# Atxmega_Board.net
KiCad netlist of a schematic drawn in EAGLE
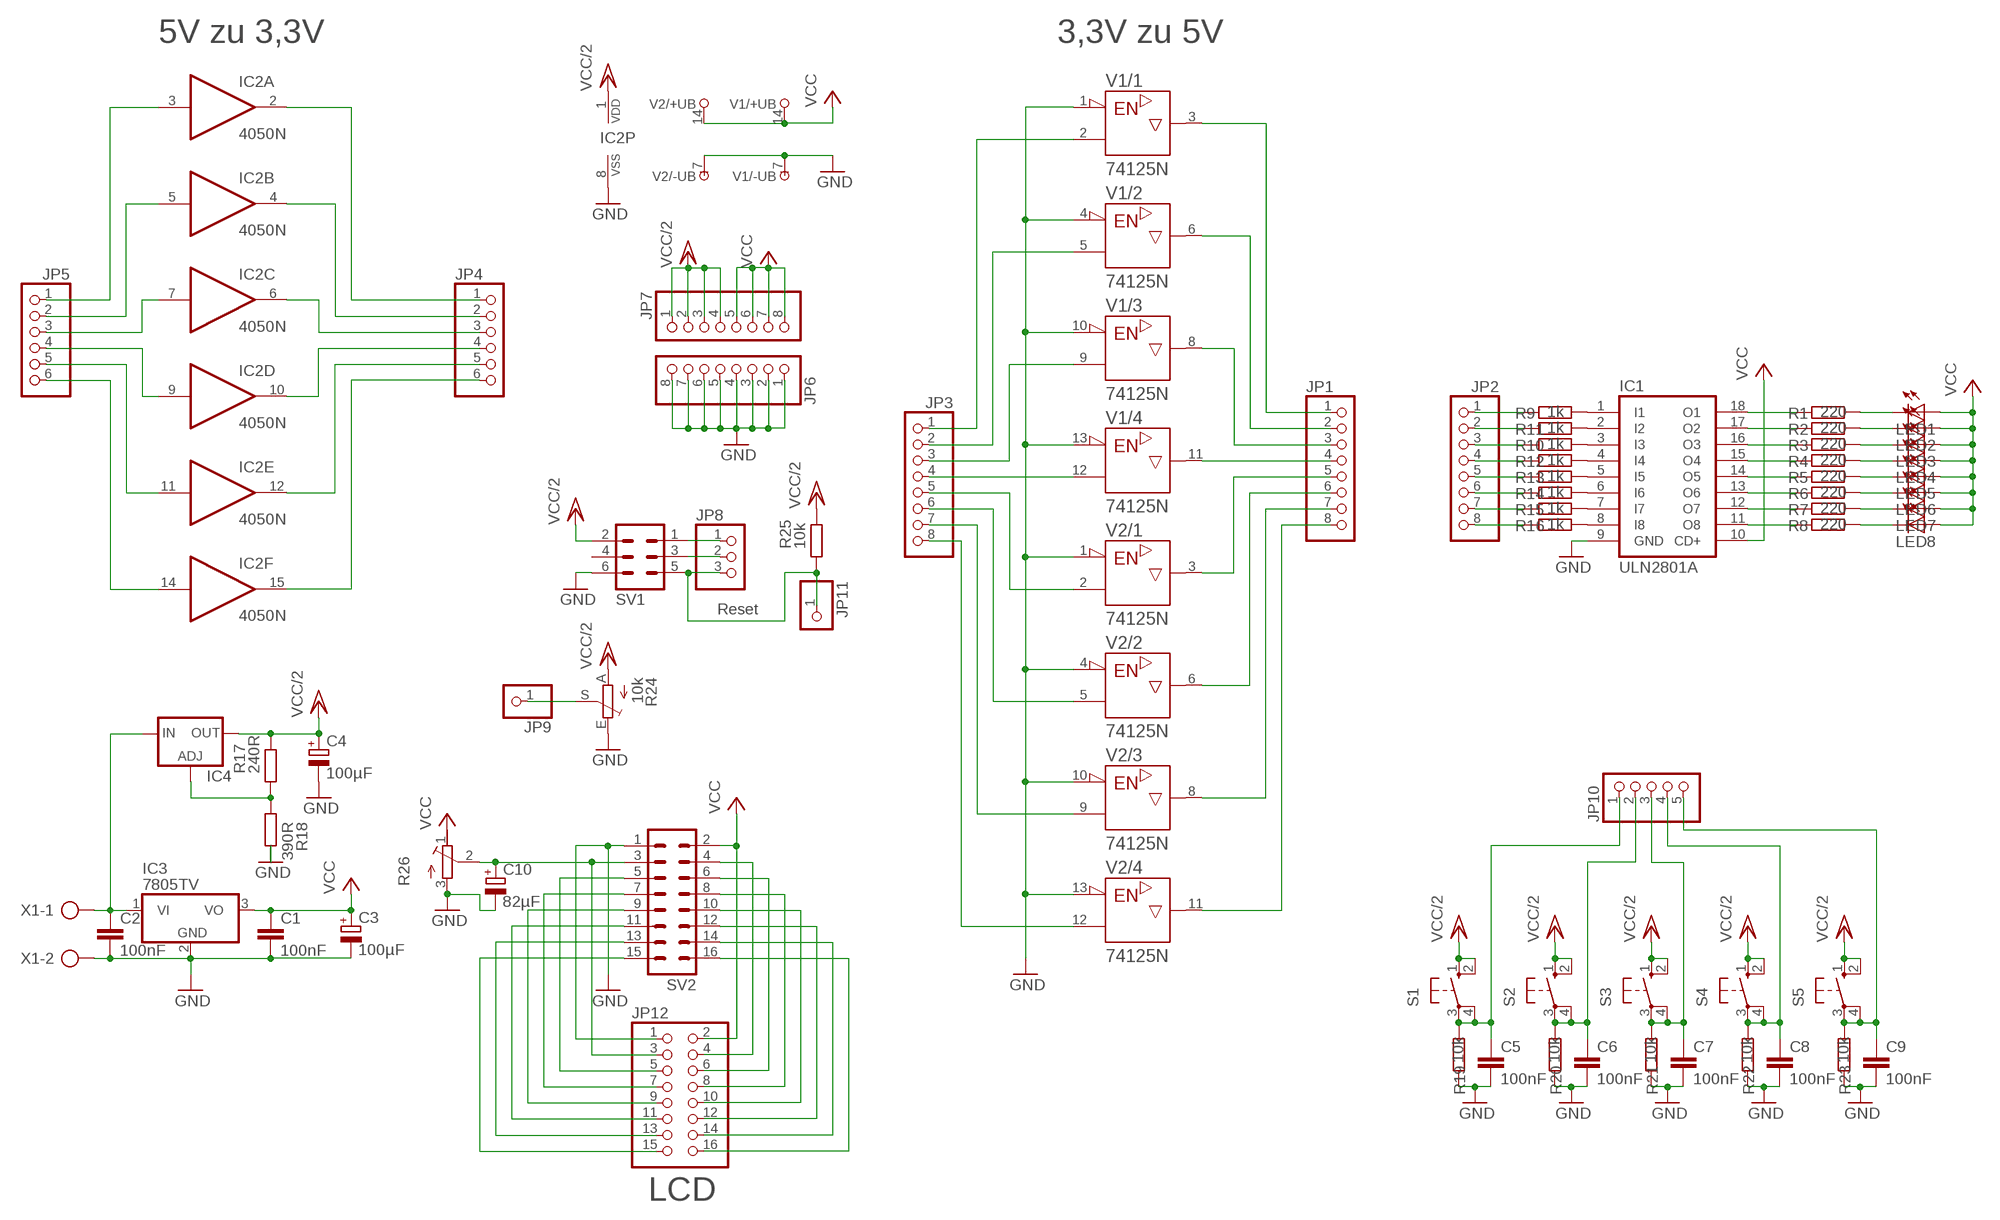
[diagram p0: schematic, sheet 1]

(export (version "E")
  (design (tool "Eeschema 10.0.6"))
  (components
    (comp (ref "C1")
      (value "100nF")
      (footprint "eagle-import:C025_050-025X075")
      (libsource (lib "eagle-import") (part "C-EU025_050-025X075"))
    )
    (comp (ref "C2")
      (value "100nF")
      (footprint "eagle-import:C025_050-025X075")
      (libsource (lib "eagle-import") (part "C-EU025_050-025X075"))
    )
    (comp (ref "C3")
      (value "100µF")
      (footprint "eagle-import:E2,5-7")
      (libsource (lib "eagle-import") (part "CPOL-EUE2.5-7"))
    )
    (comp (ref "C4")
      (value "100µF")
      (footprint "eagle-import:E2,5-7")
      (libsource (lib "eagle-import") (part "CPOL-EUE2.5-7"))
    )
    (comp (ref "C5")
      (value "100nF")
      (footprint "eagle-import:C025_050-025X075")
      (libsource (lib "eagle-import") (part "C-EU025_050-025X075"))
    )
    (comp (ref "C6")
      (value "100nF")
      (footprint "eagle-import:C025_050-025X075")
      (libsource (lib "eagle-import") (part "C-EU025_050-025X075"))
    )
    (comp (ref "C7")
      (value "100nF")
      (footprint "eagle-import:C025_050-025X075")
      (libsource (lib "eagle-import") (part "C-EU025_050-025X075"))
    )
    (comp (ref "C8")
      (value "100nF")
      (footprint "eagle-import:C025_050-025X075")
      (libsource (lib "eagle-import") (part "C-EU025_050-025X075"))
    )
    (comp (ref "C9")
      (value "100nF")
      (footprint "eagle-import:C025_050-025X075")
      (libsource (lib "eagle-import") (part "C-EU025_050-025X075"))
    )
    (comp (ref "C10")
      (value "82µF")
      (footprint "eagle-import:E2,5-7")
      (libsource (lib "eagle-import") (part "CPOL-EUE2.5-7"))
    )
    (comp (ref "IC1")
      (value "ULN2801A")
      (footprint "eagle-import:DIL18")
      (libsource (lib "eagle-import") (part "ULN2801A"))
    )
    (comp (ref "IC2")
      (value "4050N")
      (footprint "eagle-import:DIL16")
      (libsource (lib "eagle-import") (part "4050N"))
    )
    (comp (ref "IC3")
      (value "7805TV")
      (footprint "eagle-import:TO220V")
      (libsource (lib "eagle-import") (part "78TV05"))
    )
    (comp (ref "IC4")
      (value "LM317TS")
      (footprint "eagle-import:317TS")
      (libsource (lib "eagle-import") (part "LM317TS"))
    )
    (comp (ref "JP1")
      (value "PINHD-1X8")
      (footprint "eagle-import:1X08")
      (libsource (lib "eagle-import") (part "PINHD-1X8"))
    )
    (comp (ref "JP2")
      (value "PINHD-1X8")
      (footprint "eagle-import:1X08")
      (libsource (lib "eagle-import") (part "PINHD-1X8"))
    )
    (comp (ref "JP3")
      (value "PINHD-1X8")
      (footprint "eagle-import:1X08")
      (libsource (lib "eagle-import") (part "PINHD-1X8"))
    )
    (comp (ref "JP4")
      (value "PINHD-1X6")
      (footprint "eagle-import:1X06")
      (libsource (lib "eagle-import") (part "PINHD-1X6"))
    )
    (comp (ref "JP5")
      (value "PINHD-1X6")
      (footprint "eagle-import:1X06")
      (libsource (lib "eagle-import") (part "PINHD-1X6"))
    )
    (comp (ref "JP6")
      (value "PINHD-1X8")
      (footprint "eagle-import:1X08")
      (libsource (lib "eagle-import") (part "PINHD-1X8"))
    )
    (comp (ref "JP7")
      (value "PINHD-1X8")
      (footprint "eagle-import:1X08")
      (libsource (lib "eagle-import") (part "PINHD-1X8"))
    )
    (comp (ref "JP8")
      (value "PINHD-1X3")
      (footprint "eagle-import:1X03")
      (libsource (lib "eagle-import") (part "PINHD-1X3"))
    )
    (comp (ref "JP9")
      (value "PINHD-1X1")
      (footprint "eagle-import:1X01")
      (libsource (lib "eagle-import") (part "PINHD-1X1"))
    )
    (comp (ref "JP10")
      (value "PINHD-1X5")
      (footprint "eagle-import:1X05")
      (libsource (lib "eagle-import") (part "PINHD-1X5"))
    )
    (comp (ref "JP11")
      (value "PINHD-1X1")
      (footprint "eagle-import:1X01")
      (libsource (lib "eagle-import") (part "PINHD-1X1"))
    )
    (comp (ref "JP12")
      (value "PINHD-2X8")
      (footprint "eagle-import:2X08")
      (libsource (lib "eagle-import") (part "PINHD-2X8"))
    )
    (comp (ref "LED1")
      (value "LED5MM")
      (footprint "eagle-import:LED5MM")
      (libsource (lib "eagle-import") (part "LED5MM"))
    )
    (comp (ref "LED2")
      (value "LED5MM")
      (footprint "eagle-import:LED5MM")
      (libsource (lib "eagle-import") (part "LED5MM"))
    )
    (comp (ref "LED3")
      (value "LED5MM")
      (footprint "eagle-import:LED5MM")
      (libsource (lib "eagle-import") (part "LED5MM"))
    )
    (comp (ref "LED4")
      (value "LED5MM")
      (footprint "eagle-import:LED5MM")
      (libsource (lib "eagle-import") (part "LED5MM"))
    )
    (comp (ref "LED5")
      (value "LED5MM")
      (footprint "eagle-import:LED5MM")
      (libsource (lib "eagle-import") (part "LED5MM"))
    )
    (comp (ref "LED6")
      (value "LED5MM")
      (footprint "eagle-import:LED5MM")
      (libsource (lib "eagle-import") (part "LED5MM"))
    )
    (comp (ref "LED7")
      (value "LED5MM")
      (footprint "eagle-import:LED5MM")
      (libsource (lib "eagle-import") (part "LED5MM"))
    )
    (comp (ref "LED8")
      (value "LED5MM")
      (footprint "eagle-import:LED5MM")
      (libsource (lib "eagle-import") (part "LED5MM"))
    )
    (comp (ref "R1")
      (value "220")
      (footprint "eagle-import:0207_10")
      (libsource (lib "eagle-import") (part "R-EU_0207/10"))
    )
    (comp (ref "R2")
      (value "220")
      (footprint "eagle-import:0207_10")
      (libsource (lib "eagle-import") (part "R-EU_0207/10"))
    )
    (comp (ref "R3")
      (value "220")
      (footprint "eagle-import:0207_10")
      (libsource (lib "eagle-import") (part "R-EU_0207/10"))
    )
    (comp (ref "R4")
      (value "220")
      (footprint "eagle-import:0207_10")
      (libsource (lib "eagle-import") (part "R-EU_0207/10"))
    )
    (comp (ref "R5")
      (value "220")
      (footprint "eagle-import:0207_10")
      (libsource (lib "eagle-import") (part "R-EU_0207/10"))
    )
    (comp (ref "R6")
      (value "220")
      (footprint "eagle-import:0207_10")
      (libsource (lib "eagle-import") (part "R-EU_0207/10"))
    )
    (comp (ref "R7")
      (value "220")
      (footprint "eagle-import:0207_10")
      (libsource (lib "eagle-import") (part "R-EU_0207/10"))
    )
    (comp (ref "R8")
      (value "220")
      (footprint "eagle-import:0207_10")
      (libsource (lib "eagle-import") (part "R-EU_0207/10"))
    )
    (comp (ref "R9")
      (value "1k")
      (footprint "eagle-import:0207_10")
      (libsource (lib "eagle-import") (part "R-EU_0207/10"))
    )
    (comp (ref "R10")
      (value "1k")
      (footprint "eagle-import:0207_10")
      (libsource (lib "eagle-import") (part "R-EU_0207/10"))
    )
    (comp (ref "R11")
      (value "1k")
      (footprint "eagle-import:0207_10")
      (libsource (lib "eagle-import") (part "R-EU_0207/10"))
    )
    (comp (ref "R12")
      (value "1k")
      (footprint "eagle-import:0207_10")
      (libsource (lib "eagle-import") (part "R-EU_0207/10"))
    )
    (comp (ref "R13")
      (value "1k")
      (footprint "eagle-import:0207_10")
      (libsource (lib "eagle-import") (part "R-EU_0207/10"))
    )
    (comp (ref "R14")
      (value "1k")
      (footprint "eagle-import:0207_10")
      (libsource (lib "eagle-import") (part "R-EU_0207/10"))
    )
    (comp (ref "R15")
      (value "1k")
      (footprint "eagle-import:0207_10")
      (libsource (lib "eagle-import") (part "R-EU_0207/10"))
    )
    (comp (ref "R16")
      (value "1k")
      (footprint "eagle-import:0207_10")
      (libsource (lib "eagle-import") (part "R-EU_0207/10"))
    )
    (comp (ref "R17")
      (value "240R")
      (footprint "eagle-import:0207_10")
      (libsource (lib "eagle-import") (part "R-EU_0207/10"))
    )
    (comp (ref "R18")
      (value "390R")
      (footprint "eagle-import:0207_10")
      (libsource (lib "eagle-import") (part "R-EU_0207/10"))
    )
    (comp (ref "R19")
      (value "10k")
      (footprint "eagle-import:0207_10")
      (libsource (lib "eagle-import") (part "R-EU_0207/10"))
    )
    (comp (ref "R20")
      (value "10k")
      (footprint "eagle-import:0207_10")
      (libsource (lib "eagle-import") (part "R-EU_0207/10"))
    )
    (comp (ref "R21")
      (value "10k")
      (footprint "eagle-import:0207_10")
      (libsource (lib "eagle-import") (part "R-EU_0207/10"))
    )
    (comp (ref "R22")
      (value "10k")
      (footprint "eagle-import:0207_10")
      (libsource (lib "eagle-import") (part "R-EU_0207/10"))
    )
    (comp (ref "R23")
      (value "10k")
      (footprint "eagle-import:0207_10")
      (libsource (lib "eagle-import") (part "R-EU_0207/10"))
    )
    (comp (ref "R24")
      (value "10k")
      (footprint "eagle-import:ST15")
      (libsource (lib "eagle-import") (part "TRIM_EU-ST15"))
    )
    (comp (ref "R25")
      (value "10k")
      (footprint "eagle-import:0207_10")
      (libsource (lib "eagle-import") (part "R-EU_0207/10"))
    )
    (comp (ref "R26")
      (value "R-TRIMM3006P")
      (footprint "eagle-import:RTRIM3006P")
      (libsource (lib "eagle-import") (part "R-TRIMM3006P"))
    )
    (comp (ref "S1")
      (value "10-XX")
      (footprint "eagle-import:B3F-10XX")
      (fields (field (name "MPN") "B3F-1000"))
      (libsource (lib "eagle-import") (part "10-XX"))
    )
    (comp (ref "S2")
      (value "10-XX")
      (footprint "eagle-import:B3F-10XX")
      (fields (field (name "MPN") "B3F-1000"))
      (libsource (lib "eagle-import") (part "10-XX"))
    )
    (comp (ref "S3")
      (value "10-XX")
      (footprint "eagle-import:B3F-10XX")
      (fields (field (name "MPN") "B3F-1000"))
      (libsource (lib "eagle-import") (part "10-XX"))
    )
    (comp (ref "S4")
      (value "10-XX")
      (footprint "eagle-import:B3F-10XX")
      (fields (field (name "MPN") "B3F-1000"))
      (libsource (lib "eagle-import") (part "10-XX"))
    )
    (comp (ref "S5")
      (value "10-XX")
      (footprint "eagle-import:B3F-10XX")
      (fields (field (name "MPN") "B3F-1000"))
      (libsource (lib "eagle-import") (part "10-XX"))
    )
    (comp (ref "SV1")
      (value "ML6")
      (footprint "eagle-import:ML6")
      (libsource (lib "eagle-import") (part "ML6"))
    )
    (comp (ref "SV2")
      (value "ML16")
      (footprint "eagle-import:ML16")
      (libsource (lib "eagle-import") (part "ML16"))
    )
    (comp (ref "V1")
      (value "74125N")
      (footprint "eagle-import:DIL14")
      (libsource (lib "eagle-import") (part "74125N"))
    )
    (comp (ref "V2")
      (value "74125N")
      (footprint "eagle-import:DIL14")
      (libsource (lib "eagle-import") (part "74125N"))
    )
    (comp (ref "X1")
      (value "AK500/2")
      (footprint "eagle-import:AK500_2")
      (libsource (lib "eagle-import") (part "AK500/2"))
    )
  )
  (nets
    (net (code "1") (name "GND") (class "Default")
      (node (ref "C1") (pin "2") (pinfunction "2_2") (pintype "passive"))
      (node (ref "C10") (pin "-") (pinfunction "-_-") (pintype "passive"))
      (node (ref "C2") (pin "2") (pinfunction "2_2") (pintype "passive"))
      (node (ref "C3") (pin "-") (pinfunction "-_-") (pintype "passive"))
      (node (ref "C4") (pin "-") (pinfunction "-_-") (pintype "passive"))
      (node (ref "C5") (pin "2") (pinfunction "2_2") (pintype "passive"))
      (node (ref "C6") (pin "2") (pinfunction "2_2") (pintype "passive"))
      (node (ref "C7") (pin "2") (pinfunction "2_2") (pintype "passive"))
      (node (ref "C8") (pin "2") (pinfunction "2_2") (pintype "passive"))
      (node (ref "C9") (pin "2") (pinfunction "2_2") (pintype "passive"))
      (node (ref "IC1") (pin "9") (pinfunction "GND_9") (pintype "power_in"))
      (node (ref "IC2") (pin "8") (pinfunction "VSS_8") (pintype "power_in"))
      (node (ref "IC3") (pin "2") (pinfunction "GND_2") (pintype "passive"))
      (node (ref "JP12") (pin "1") (pinfunction "1_1") (pintype "passive"))
      (node (ref "JP6") (pin "1") (pinfunction "1_1") (pintype "passive"))
      (node (ref "JP6") (pin "2") (pinfunction "2_2") (pintype "passive"))
      (node (ref "JP6") (pin "3") (pinfunction "3_3") (pintype "passive"))
      (node (ref "JP6") (pin "4") (pinfunction "4_4") (pintype "passive"))
      (node (ref "JP6") (pin "5") (pinfunction "5_5") (pintype "passive"))
      (node (ref "JP6") (pin "6") (pinfunction "6_6") (pintype "passive"))
      (node (ref "JP6") (pin "7") (pinfunction "7_7") (pintype "passive"))
      (node (ref "JP6") (pin "8") (pinfunction "8_8") (pintype "passive"))
      (node (ref "R18") (pin "2") (pinfunction "2_2") (pintype "passive"))
      (node (ref "R19") (pin "1") (pinfunction "1_1") (pintype "passive"))
      (node (ref "R20") (pin "1") (pinfunction "1_1") (pintype "passive"))
      (node (ref "R21") (pin "1") (pinfunction "1_1") (pintype "passive"))
      (node (ref "R22") (pin "1") (pinfunction "1_1") (pintype "passive"))
      (node (ref "R23") (pin "1") (pinfunction "1_1") (pintype "passive"))
      (node (ref "R24") (pin "E") (pinfunction "E_E") (pintype "passive"))
      (node (ref "R26") (pin "3") (pinfunction "E_3") (pintype "passive"))
      (node (ref "SV1") (pin "6") (pinfunction "6_6") (pintype "passive"))
      (node (ref "SV2") (pin "1") (pinfunction "1_1") (pintype "passive"))
      (node (ref "V1") (pin "1") (pinfunction "~{G}_1") (pintype "input"))
      (node (ref "V1") (pin "10") (pinfunction "~{G}_10") (pintype "input"))
      (node (ref "V1") (pin "13") (pinfunction "~{G}_13") (pintype "input"))
      (node (ref "V1") (pin "4") (pinfunction "~{G}_4") (pintype "input"))
      (node (ref "V1") (pin "7") (pinfunction "-UB_7") (pintype "power_in"))
      (node (ref "V2") (pin "1") (pinfunction "~{G}_1") (pintype "input"))
      (node (ref "V2") (pin "10") (pinfunction "~{G}_10") (pintype "input"))
      (node (ref "V2") (pin "13") (pinfunction "~{G}_13") (pintype "input"))
      (node (ref "V2") (pin "4") (pinfunction "~{G}_4") (pintype "input"))
      (node (ref "V2") (pin "7") (pinfunction "-UB_7") (pintype "power_in"))
      (node (ref "X1") (pin "2") (pinfunction "KL_2") (pintype "passive"))
    )
    (net (code "2") (name "Net-(IC1-I1)") (class "Default")
      (node (ref "IC1") (pin "1") (pinfunction "I1_1") (pintype "input"))
      (node (ref "R9") (pin "2") (pinfunction "2_2") (pintype "passive"))
    )
    (net (code "3") (name "Net-(IC1-I2)") (class "Default")
      (node (ref "IC1") (pin "2") (pinfunction "I2_2") (pintype "input"))
      (node (ref "R11") (pin "2") (pinfunction "2_2") (pintype "passive"))
    )
    (net (code "4") (name "Net-(IC1-I3)") (class "Default")
      (node (ref "IC1") (pin "3") (pinfunction "I3_3") (pintype "input"))
      (node (ref "R10") (pin "2") (pinfunction "2_2") (pintype "passive"))
    )
    (net (code "5") (name "Net-(IC1-I4)") (class "Default")
      (node (ref "IC1") (pin "4") (pinfunction "I4_4") (pintype "input"))
      (node (ref "R12") (pin "2") (pinfunction "2_2") (pintype "passive"))
    )
    (net (code "6") (name "Net-(IC1-I5)") (class "Default")
      (node (ref "IC1") (pin "5") (pinfunction "I5_5") (pintype "input"))
      (node (ref "R13") (pin "2") (pinfunction "2_2") (pintype "passive"))
    )
    (net (code "7") (name "Net-(IC1-I6)") (class "Default")
      (node (ref "IC1") (pin "6") (pinfunction "I6_6") (pintype "input"))
      (node (ref "R14") (pin "2") (pinfunction "2_2") (pintype "passive"))
    )
    (net (code "8") (name "Net-(IC1-I7)") (class "Default")
      (node (ref "IC1") (pin "7") (pinfunction "I7_7") (pintype "input"))
      (node (ref "R15") (pin "2") (pinfunction "2_2") (pintype "passive"))
    )
    (net (code "9") (name "Net-(IC1-I8)") (class "Default")
      (node (ref "IC1") (pin "8") (pinfunction "I8_8") (pintype "input"))
      (node (ref "R16") (pin "2") (pinfunction "2_2") (pintype "passive"))
    )
    (net (code "10") (name "Net-(IC1-O1)") (class "Default")
      (node (ref "IC1") (pin "18") (pinfunction "O1_18") (pintype "open_collector"))
      (node (ref "R1") (pin "1") (pinfunction "1_1") (pintype "passive"))
    )
    (net (code "11") (name "Net-(IC1-O2)") (class "Default")
      (node (ref "IC1") (pin "17") (pinfunction "O2_17") (pintype "open_collector"))
      (node (ref "R2") (pin "1") (pinfunction "1_1") (pintype "passive"))
    )
    (net (code "12") (name "Net-(IC1-O3)") (class "Default")
      (node (ref "IC1") (pin "16") (pinfunction "O3_16") (pintype "open_collector"))
      (node (ref "R3") (pin "1") (pinfunction "1_1") (pintype "passive"))
    )
    (net (code "13") (name "Net-(IC1-O4)") (class "Default")
      (node (ref "IC1") (pin "15") (pinfunction "O4_15") (pintype "open_collector"))
      (node (ref "R4") (pin "1") (pinfunction "1_1") (pintype "passive"))
    )
    (net (code "14") (name "Net-(IC1-O5)") (class "Default")
      (node (ref "IC1") (pin "14") (pinfunction "O5_14") (pintype "open_collector"))
      (node (ref "R5") (pin "1") (pinfunction "1_1") (pintype "passive"))
    )
    (net (code "15") (name "Net-(IC1-O6)") (class "Default")
      (node (ref "IC1") (pin "13") (pinfunction "O6_13") (pintype "open_collector"))
      (node (ref "R6") (pin "1") (pinfunction "1_1") (pintype "passive"))
    )
    (net (code "16") (name "Net-(IC1-O7)") (class "Default")
      (node (ref "IC1") (pin "12") (pinfunction "O7_12") (pintype "open_collector"))
      (node (ref "R7") (pin "1") (pinfunction "1_1") (pintype "passive"))
    )
    (net (code "17") (name "Net-(IC1-O8)") (class "Default")
      (node (ref "IC1") (pin "11") (pinfunction "O8_11") (pintype "open_collector"))
      (node (ref "R8") (pin "1") (pinfunction "1_1") (pintype "passive"))
    )
    (net (code "18") (name "Net-(IC2A-I)") (class "Default")
      (node (ref "IC2") (pin "3") (pinfunction "I_3") (pintype "input"))
      (node (ref "JP5") (pin "1") (pinfunction "1_1") (pintype "passive"))
    )
    (net (code "19") (name "Net-(IC2A-O)") (class "Default")
      (node (ref "IC2") (pin "2") (pinfunction "O_2") (pintype "output"))
      (node (ref "JP4") (pin "1") (pinfunction "1_1") (pintype "passive"))
    )
    (net (code "20") (name "Net-(IC2B-I)") (class "Default")
      (node (ref "IC2") (pin "5") (pinfunction "I_5") (pintype "input"))
      (node (ref "JP5") (pin "2") (pinfunction "2_2") (pintype "passive"))
    )
    (net (code "21") (name "Net-(IC2B-O)") (class "Default")
      (node (ref "IC2") (pin "4") (pinfunction "O_4") (pintype "output"))
      (node (ref "JP4") (pin "2") (pinfunction "2_2") (pintype "passive"))
    )
    (net (code "22") (name "Net-(IC2C-I)") (class "Default")
      (node (ref "IC2") (pin "7") (pinfunction "I_7") (pintype "input"))
      (node (ref "JP5") (pin "3") (pinfunction "3_3") (pintype "passive"))
    )
    (net (code "23") (name "Net-(IC2C-O)") (class "Default")
      (node (ref "IC2") (pin "6") (pinfunction "O_6") (pintype "output"))
      (node (ref "JP4") (pin "3") (pinfunction "3_3") (pintype "passive"))
    )
    (net (code "24") (name "Net-(IC2D-I)") (class "Default")
      (node (ref "IC2") (pin "9") (pinfunction "I_9") (pintype "input"))
      (node (ref "JP5") (pin "4") (pinfunction "4_4") (pintype "passive"))
    )
    (net (code "25") (name "Net-(IC2D-O)") (class "Default")
      (node (ref "IC2") (pin "10") (pinfunction "O_10") (pintype "output"))
      (node (ref "JP4") (pin "4") (pinfunction "4_4") (pintype "passive"))
    )
    (net (code "26") (name "Net-(IC2E-I)") (class "Default")
      (node (ref "IC2") (pin "11") (pinfunction "I_11") (pintype "input"))
      (node (ref "JP5") (pin "5") (pinfunction "5_5") (pintype "passive"))
    )
    (net (code "27") (name "Net-(IC2E-O)") (class "Default")
      (node (ref "IC2") (pin "12") (pinfunction "O_12") (pintype "output"))
      (node (ref "JP4") (pin "5") (pinfunction "5_5") (pintype "passive"))
    )
    (net (code "28") (name "Net-(IC2F-I)") (class "Default")
      (node (ref "IC2") (pin "14") (pinfunction "I_14") (pintype "input"))
      (node (ref "JP5") (pin "6") (pinfunction "6_6") (pintype "passive"))
    )
    (net (code "29") (name "Net-(IC2F-O)") (class "Default")
      (node (ref "IC2") (pin "15") (pinfunction "O_15") (pintype "output"))
      (node (ref "JP4") (pin "6") (pinfunction "6_6") (pintype "passive"))
    )
    (net (code "30") (name "Net-(IC3-VI)") (class "Default")
      (node (ref "C2") (pin "1") (pinfunction "1_1") (pintype "passive"))
      (node (ref "IC3") (pin "1") (pinfunction "VI_1") (pintype "input"))
      (node (ref "IC4") (pin "3") (pinfunction "IN_3") (pintype "input"))
      (node (ref "X1") (pin "1") (pinfunction "KL_1") (pintype "passive"))
    )
    (net (code "31") (name "Net-(IC4-ADJ)") (class "Default")
      (node (ref "IC4") (pin "1") (pinfunction "ADJ_1") (pintype "input"))
      (node (ref "R17") (pin "1") (pinfunction "1_1") (pintype "passive"))
      (node (ref "R18") (pin "1") (pinfunction "1_1") (pintype "passive"))
    )
    (net (code "32") (name "Net-(JP2-Pad1)") (class "Default")
      (node (ref "JP2") (pin "1") (pinfunction "1_1") (pintype "passive"))
      (node (ref "R9") (pin "1") (pinfunction "1_1") (pintype "passive"))
    )
    (net (code "33") (name "Net-(JP2-Pad2)") (class "Default")
      (node (ref "JP2") (pin "2") (pinfunction "2_2") (pintype "passive"))
      (node (ref "R11") (pin "1") (pinfunction "1_1") (pintype "passive"))
    )
    (net (code "34") (name "Net-(JP2-Pad3)") (class "Default")
      (node (ref "JP2") (pin "3") (pinfunction "3_3") (pintype "passive"))
      (node (ref "R10") (pin "1") (pinfunction "1_1") (pintype "passive"))
    )
    (net (code "35") (name "Net-(JP2-Pad4)") (class "Default")
      (node (ref "JP2") (pin "4") (pinfunction "4_4") (pintype "passive"))
      (node (ref "R12") (pin "1") (pinfunction "1_1") (pintype "passive"))
    )
    (net (code "36") (name "Net-(JP2-Pad5)") (class "Default")
      (node (ref "JP2") (pin "5") (pinfunction "5_5") (pintype "passive"))
      (node (ref "R13") (pin "1") (pinfunction "1_1") (pintype "passive"))
    )
    (net (code "37") (name "Net-(JP2-Pad6)") (class "Default")
      (node (ref "JP2") (pin "6") (pinfunction "6_6") (pintype "passive"))
      (node (ref "R14") (pin "1") (pinfunction "1_1") (pintype "passive"))
    )
    (net (code "38") (name "Net-(JP2-Pad7)") (class "Default")
      (node (ref "JP2") (pin "7") (pinfunction "7_7") (pintype "passive"))
      (node (ref "R15") (pin "1") (pinfunction "1_1") (pintype "passive"))
    )
    (net (code "39") (name "Net-(JP2-Pad8)") (class "Default")
      (node (ref "JP2") (pin "8") (pinfunction "8_8") (pintype "passive"))
      (node (ref "R16") (pin "1") (pinfunction "1_1") (pintype "passive"))
    )
    (net (code "40") (name "Net-(JP8-Pad1)") (class "Default")
      (node (ref "JP8") (pin "1") (pinfunction "1_1") (pintype "passive"))
      (node (ref "SV1") (pin "1") (pinfunction "1_1") (pintype "passive"))
    )
    (net (code "41") (name "Net-(JP8-Pad2)") (class "Default")
      (node (ref "JP8") (pin "2") (pinfunction "2_2") (pintype "passive"))
      (node (ref "SV1") (pin "3") (pinfunction "3_3") (pintype "passive"))
    )
    (net (code "42") (name "Net-(JP9-Pad1)") (class "Default")
      (node (ref "JP9") (pin "1") (pinfunction "1_1") (pintype "passive"))
      (node (ref "R24") (pin "S") (pinfunction "S_S") (pintype "passive"))
    )
    (net (code "43") (name "Net-(JP11-Pad1)") (class "Default")
      (node (ref "JP11") (pin "1") (pinfunction "1_1") (pintype "passive"))
      (node (ref "JP8") (pin "3") (pinfunction "3_3") (pintype "passive"))
      (node (ref "R25") (pin "1") (pinfunction "1_1") (pintype "passive"))
      (node (ref "SV1") (pin "5") (pinfunction "5_5") (pintype "passive"))
    )
    (net (code "44") (name "Net-(JP12-Pad4)") (class "Default")
      (node (ref "JP12") (pin "4") (pinfunction "4_4") (pintype "passive"))
      (node (ref "SV2") (pin "4") (pinfunction "4_4") (pintype "passive"))
    )
    (net (code "45") (name "Net-(JP12-Pad5)") (class "Default")
      (node (ref "JP12") (pin "5") (pinfunction "5_5") (pintype "passive"))
      (node (ref "SV2") (pin "5") (pinfunction "5_5") (pintype "passive"))
    )
    (net (code "46") (name "Net-(JP12-Pad6)") (class "Default")
      (node (ref "JP12") (pin "6") (pinfunction "6_6") (pintype "passive"))
      (node (ref "SV2") (pin "6") (pinfunction "6_6") (pintype "passive"))
    )
    (net (code "47") (name "Net-(JP12-Pad7)") (class "Default")
      (node (ref "JP12") (pin "7") (pinfunction "7_7") (pintype "passive"))
      (node (ref "SV2") (pin "7") (pinfunction "7_7") (pintype "passive"))
    )
    (net (code "48") (name "Net-(JP12-Pad8)") (class "Default")
      (node (ref "JP12") (pin "8") (pinfunction "8_8") (pintype "passive"))
      (node (ref "SV2") (pin "8") (pinfunction "8_8") (pintype "passive"))
    )
    (net (code "49") (name "Net-(JP12-Pad9)") (class "Default")
      (node (ref "JP12") (pin "9") (pinfunction "9_9") (pintype "passive"))
      (node (ref "SV2") (pin "9") (pinfunction "9_9") (pintype "passive"))
    )
    (net (code "50") (name "Net-(JP12-Pad10)") (class "Default")
      (node (ref "JP12") (pin "10") (pinfunction "10_10") (pintype "passive"))
      (node (ref "SV2") (pin "10") (pinfunction "10_10") (pintype "passive"))
    )
    (net (code "51") (name "Net-(JP12-Pad11)") (class "Default")
      (node (ref "JP12") (pin "11") (pinfunction "11_11") (pintype "passive"))
      (node (ref "SV2") (pin "11") (pinfunction "11_11") (pintype "passive"))
    )
    (net (code "52") (name "Net-(JP12-Pad12)") (class "Default")
      (node (ref "JP12") (pin "12") (pinfunction "12_12") (pintype "passive"))
      (node (ref "SV2") (pin "12") (pinfunction "12_12") (pintype "passive"))
    )
    (net (code "53") (name "Net-(JP12-Pad13)") (class "Default")
      (node (ref "JP12") (pin "13") (pinfunction "13_13") (pintype "passive"))
      (node (ref "SV2") (pin "13") (pinfunction "13_13") (pintype "passive"))
    )
    (net (code "54") (name "Net-(JP12-Pad14)") (class "Default")
      (node (ref "JP12") (pin "14") (pinfunction "14_14") (pintype "passive"))
      (node (ref "SV2") (pin "14") (pinfunction "14_14") (pintype "passive"))
    )
    (net (code "55") (name "Net-(JP12-Pad15)") (class "Default")
      (node (ref "JP12") (pin "15") (pinfunction "15_15") (pintype "passive"))
      (node (ref "SV2") (pin "15") (pinfunction "15_15") (pintype "passive"))
    )
    (net (code "56") (name "Net-(JP12-Pad16)") (class "Default")
      (node (ref "JP12") (pin "16") (pinfunction "16_16") (pintype "passive"))
      (node (ref "SV2") (pin "16") (pinfunction "16_16") (pintype "passive"))
    )
    (net (code "57") (name "Net-(LED1-C)") (class "Default")
      (node (ref "LED1") (pin "K") (pinfunction "C_K") (pintype "passive"))
      (node (ref "R1") (pin "2") (pinfunction "2_2") (pintype "passive"))
    )
    (net (code "58") (name "Net-(LED2-C)") (class "Default")
      (node (ref "LED2") (pin "K") (pinfunction "C_K") (pintype "passive"))
      (node (ref "R2") (pin "2") (pinfunction "2_2") (pintype "passive"))
    )
    (net (code "59") (name "Net-(LED3-C)") (class "Default")
      (node (ref "LED3") (pin "K") (pinfunction "C_K") (pintype "passive"))
      (node (ref "R3") (pin "2") (pinfunction "2_2") (pintype "passive"))
    )
    (net (code "60") (name "Net-(LED4-C)") (class "Default")
      (node (ref "LED4") (pin "K") (pinfunction "C_K") (pintype "passive"))
      (node (ref "R4") (pin "2") (pinfunction "2_2") (pintype "passive"))
    )
    (net (code "61") (name "Net-(LED5-C)") (class "Default")
      (node (ref "LED5") (pin "K") (pinfunction "C_K") (pintype "passive"))
      (node (ref "R5") (pin "2") (pinfunction "2_2") (pintype "passive"))
    )
    (net (code "62") (name "Net-(LED6-C)") (class "Default")
      (node (ref "LED6") (pin "K") (pinfunction "C_K") (pintype "passive"))
      (node (ref "R6") (pin "2") (pinfunction "2_2") (pintype "passive"))
    )
    (net (code "63") (name "Net-(LED7-C)") (class "Default")
      (node (ref "LED7") (pin "K") (pinfunction "C_K") (pintype "passive"))
      (node (ref "R7") (pin "2") (pinfunction "2_2") (pintype "passive"))
    )
    (net (code "64") (name "Net-(LED8-C)") (class "Default")
      (node (ref "LED8") (pin "K") (pinfunction "C_K") (pintype "passive"))
      (node (ref "R8") (pin "2") (pinfunction "2_2") (pintype "passive"))
    )
    (net (code "65") (name "Net-(R26-S)") (class "Default")
      (node (ref "C10") (pin "+") (pinfunction "+_+") (pintype "passive"))
      (node (ref "JP12") (pin "3") (pinfunction "3_3") (pintype "passive"))
      (node (ref "R26") (pin "2") (pinfunction "S_2") (pintype "passive"))
      (node (ref "SV2") (pin "3") (pinfunction "3_3") (pintype "passive"))
    )
    (net (code "66") (name "Net-(S1-P)") (class "Default")
      (node (ref "C5") (pin "1") (pinfunction "1_1") (pintype "passive"))
      (node (ref "JP10") (pin "1") (pinfunction "1_1") (pintype "passive"))
      (node (ref "R19") (pin "2") (pinfunction "2_2") (pintype "passive"))
      (node (ref "S1") (pin "3") (pinfunction "P_3") (pintype "passive"))
      (node (ref "S1") (pin "4") (pinfunction "P1_4") (pintype "passive"))
    )
    (net (code "67") (name "Net-(S2-P)") (class "Default")
      (node (ref "C6") (pin "1") (pinfunction "1_1") (pintype "passive"))
      (node (ref "JP10") (pin "2") (pinfunction "2_2") (pintype "passive"))
      (node (ref "R20") (pin "2") (pinfunction "2_2") (pintype "passive"))
      (node (ref "S2") (pin "3") (pinfunction "P_3") (pintype "passive"))
      (node (ref "S2") (pin "4") (pinfunction "P1_4") (pintype "passive"))
    )
    (net (code "68") (name "Net-(S3-P)") (class "Default")
      (node (ref "C7") (pin "1") (pinfunction "1_1") (pintype "passive"))
      (node (ref "JP10") (pin "3") (pinfunction "3_3") (pintype "passive"))
      (node (ref "R21") (pin "2") (pinfunction "2_2") (pintype "passive"))
      (node (ref "S3") (pin "3") (pinfunction "P_3") (pintype "passive"))
      (node (ref "S3") (pin "4") (pinfunction "P1_4") (pintype "passive"))
    )
    (net (code "69") (name "Net-(S4-P)") (class "Default")
      (node (ref "C8") (pin "1") (pinfunction "1_1") (pintype "passive"))
      (node (ref "JP10") (pin "4") (pinfunction "4_4") (pintype "passive"))
      (node (ref "R22") (pin "2") (pinfunction "2_2") (pintype "passive"))
      (node (ref "S4") (pin "3") (pinfunction "P_3") (pintype "passive"))
      (node (ref "S4") (pin "4") (pinfunction "P1_4") (pintype "passive"))
    )
    (net (code "70") (name "Net-(S5-P)") (class "Default")
      (node (ref "C9") (pin "1") (pinfunction "1_1") (pintype "passive"))
      (node (ref "JP10") (pin "5") (pinfunction "5_5") (pintype "passive"))
      (node (ref "R23") (pin "2") (pinfunction "2_2") (pintype "passive"))
      (node (ref "S5") (pin "3") (pinfunction "P_3") (pintype "passive"))
      (node (ref "S5") (pin "4") (pinfunction "P1_4") (pintype "passive"))
    )
    (net (code "71") (name "Net-(V1C-A)") (class "Default")
      (node (ref "JP3") (pin "1") (pinfunction "1_1") (pintype "passive"))
      (node (ref "V1") (pin "2") (pinfunction "A_2") (pintype "input"))
    )
    (net (code "72") (name "Net-(V1C-Y)") (class "Default")
      (node (ref "JP1") (pin "1") (pinfunction "1_1") (pintype "passive"))
      (node (ref "V1") (pin "3") (pinfunction "Y_3") (pintype "tri_state"))
    )
    (net (code "73") (name "Net-(V1D-A)") (class "Default")
      (node (ref "JP3") (pin "2") (pinfunction "2_2") (pintype "passive"))
      (node (ref "V1") (pin "5") (pinfunction "A_5") (pintype "input"))
    )
    (net (code "74") (name "Net-(V1D-Y)") (class "Default")
      (node (ref "JP1") (pin "2") (pinfunction "2_2") (pintype "passive"))
      (node (ref "V1") (pin "6") (pinfunction "Y_6") (pintype "tri_state"))
    )
    (net (code "75") (name "Net-(V1E-A)") (class "Default")
      (node (ref "JP3") (pin "3") (pinfunction "3_3") (pintype "passive"))
      (node (ref "V1") (pin "9") (pinfunction "A_9") (pintype "input"))
    )
    (net (code "76") (name "Net-(V1E-Y)") (class "Default")
      (node (ref "JP1") (pin "3") (pinfunction "3_3") (pintype "passive"))
      (node (ref "V1") (pin "8") (pinfunction "Y_8") (pintype "tri_state"))
    )
    (net (code "77") (name "Net-(V1F-A)") (class "Default")
      (node (ref "JP3") (pin "4") (pinfunction "4_4") (pintype "passive"))
      (node (ref "V1") (pin "12") (pinfunction "A_12") (pintype "input"))
    )
    (net (code "78") (name "Net-(V1F-Y)") (class "Default")
      (node (ref "JP1") (pin "4") (pinfunction "4_4") (pintype "passive"))
      (node (ref "V1") (pin "11") (pinfunction "Y_11") (pintype "tri_state"))
    )
    (net (code "79") (name "Net-(V2C-A)") (class "Default")
      (node (ref "JP3") (pin "5") (pinfunction "5_5") (pintype "passive"))
      (node (ref "V2") (pin "2") (pinfunction "A_2") (pintype "input"))
    )
    (net (code "80") (name "Net-(V2C-Y)") (class "Default")
      (node (ref "JP1") (pin "5") (pinfunction "5_5") (pintype "passive"))
      (node (ref "V2") (pin "3") (pinfunction "Y_3") (pintype "tri_state"))
    )
    (net (code "81") (name "Net-(V2D-A)") (class "Default")
      (node (ref "JP3") (pin "6") (pinfunction "6_6") (pintype "passive"))
      (node (ref "V2") (pin "5") (pinfunction "A_5") (pintype "input"))
    )
    (net (code "82") (name "Net-(V2D-Y)") (class "Default")
      (node (ref "JP1") (pin "6") (pinfunction "6_6") (pintype "passive"))
      (node (ref "V2") (pin "6") (pinfunction "Y_6") (pintype "tri_state"))
    )
    (net (code "83") (name "Net-(V2E-A)") (class "Default")
      (node (ref "JP3") (pin "7") (pinfunction "7_7") (pintype "passive"))
      (node (ref "V2") (pin "9") (pinfunction "A_9") (pintype "input"))
    )
    (net (code "84") (name "Net-(V2E-Y)") (class "Default")
      (node (ref "JP1") (pin "7") (pinfunction "7_7") (pintype "passive"))
      (node (ref "V2") (pin "8") (pinfunction "Y_8") (pintype "tri_state"))
    )
    (net (code "85") (name "Net-(V2F-A)") (class "Default")
      (node (ref "JP3") (pin "8") (pinfunction "8_8") (pintype "passive"))
      (node (ref "V2") (pin "12") (pinfunction "A_12") (pintype "input"))
    )
    (net (code "86") (name "Net-(V2F-Y)") (class "Default")
      (node (ref "JP1") (pin "8") (pinfunction "8_8") (pintype "passive"))
      (node (ref "V2") (pin "11") (pinfunction "Y_11") (pintype "tri_state"))
    )
    (net (code "87") (name "VCC") (class "Default")
      (node (ref "C1") (pin "1") (pinfunction "1_1") (pintype "passive"))
      (node (ref "C3") (pin "+") (pinfunction "+_+") (pintype "passive"))
      (node (ref "IC1") (pin "10") (pinfunction "CD+_10") (pintype "passive"))
      (node (ref "IC3") (pin "3") (pinfunction "VO_3") (pintype "passive"))
      (node (ref "JP12") (pin "2") (pinfunction "2_2") (pintype "passive"))
      (node (ref "JP7") (pin "5") (pinfunction "5_5") (pintype "passive"))
      (node (ref "JP7") (pin "6") (pinfunction "6_6") (pintype "passive"))
      (node (ref "JP7") (pin "7") (pinfunction "7_7") (pintype "passive"))
      (node (ref "JP7") (pin "8") (pinfunction "8_8") (pintype "passive"))
      (node (ref "LED1") (pin "A") (pinfunction "A_A") (pintype "passive"))
      (node (ref "LED2") (pin "A") (pinfunction "A_A") (pintype "passive"))
      (node (ref "LED3") (pin "A") (pinfunction "A_A") (pintype "passive"))
      (node (ref "LED4") (pin "A") (pinfunction "A_A") (pintype "passive"))
      (node (ref "LED5") (pin "A") (pinfunction "A_A") (pintype "passive"))
      (node (ref "LED6") (pin "A") (pinfunction "A_A") (pintype "passive"))
      (node (ref "LED7") (pin "A") (pinfunction "A_A") (pintype "passive"))
      (node (ref "LED8") (pin "A") (pinfunction "A_A") (pintype "passive"))
      (node (ref "R26") (pin "1") (pinfunction "A_1") (pintype "passive"))
      (node (ref "SV2") (pin "2") (pinfunction "2_2") (pintype "passive"))
      (node (ref "V1") (pin "14") (pinfunction "+UB_14") (pintype "power_in"))
      (node (ref "V2") (pin "14") (pinfunction "+UB_14") (pintype "power_in"))
    )
    (net (code "88") (name "VCC{slash}2") (class "Default")
      (node (ref "C4") (pin "+") (pinfunction "+_+") (pintype "passive"))
      (node (ref "IC2") (pin "1") (pinfunction "VDD_1") (pintype "power_in"))
      (node (ref "IC4") (pin "2") (pinfunction "OUT_2") (pintype "passive"))
      (node (ref "JP7") (pin "1") (pinfunction "1_1") (pintype "passive"))
      (node (ref "JP7") (pin "2") (pinfunction "2_2") (pintype "passive"))
      (node (ref "JP7") (pin "3") (pinfunction "3_3") (pintype "passive"))
      (node (ref "JP7") (pin "4") (pinfunction "4_4") (pintype "passive"))
      (node (ref "R17") (pin "2") (pinfunction "2_2") (pintype "passive"))
      (node (ref "R24") (pin "A") (pinfunction "A_A") (pintype "passive"))
      (node (ref "R25") (pin "2") (pinfunction "2_2") (pintype "passive"))
      (node (ref "S1") (pin "1") (pinfunction "S_1") (pintype "passive"))
      (node (ref "S1") (pin "2") (pinfunction "S1_2") (pintype "passive"))
      (node (ref "S2") (pin "1") (pinfunction "S_1") (pintype "passive"))
      (node (ref "S2") (pin "2") (pinfunction "S1_2") (pintype "passive"))
      (node (ref "S3") (pin "1") (pinfunction "S_1") (pintype "passive"))
      (node (ref "S3") (pin "2") (pinfunction "S1_2") (pintype "passive"))
      (node (ref "S4") (pin "1") (pinfunction "S_1") (pintype "passive"))
      (node (ref "S4") (pin "2") (pinfunction "S1_2") (pintype "passive"))
      (node (ref "S5") (pin "1") (pinfunction "S_1") (pintype "passive"))
      (node (ref "S5") (pin "2") (pinfunction "S1_2") (pintype "passive"))
      (node (ref "SV1") (pin "2") (pinfunction "2_2") (pintype "passive"))
    )
    (net (code "89") (name "unconnected-(SV1-Pad4)") (class "Default")
      (node (ref "SV1") (pin "4") (pinfunction "4_4") (pintype "passive"))
    )
  )
)
